# IGauge_V_2_2.net
KiCad netlist of a schematic drawn in EAGLE
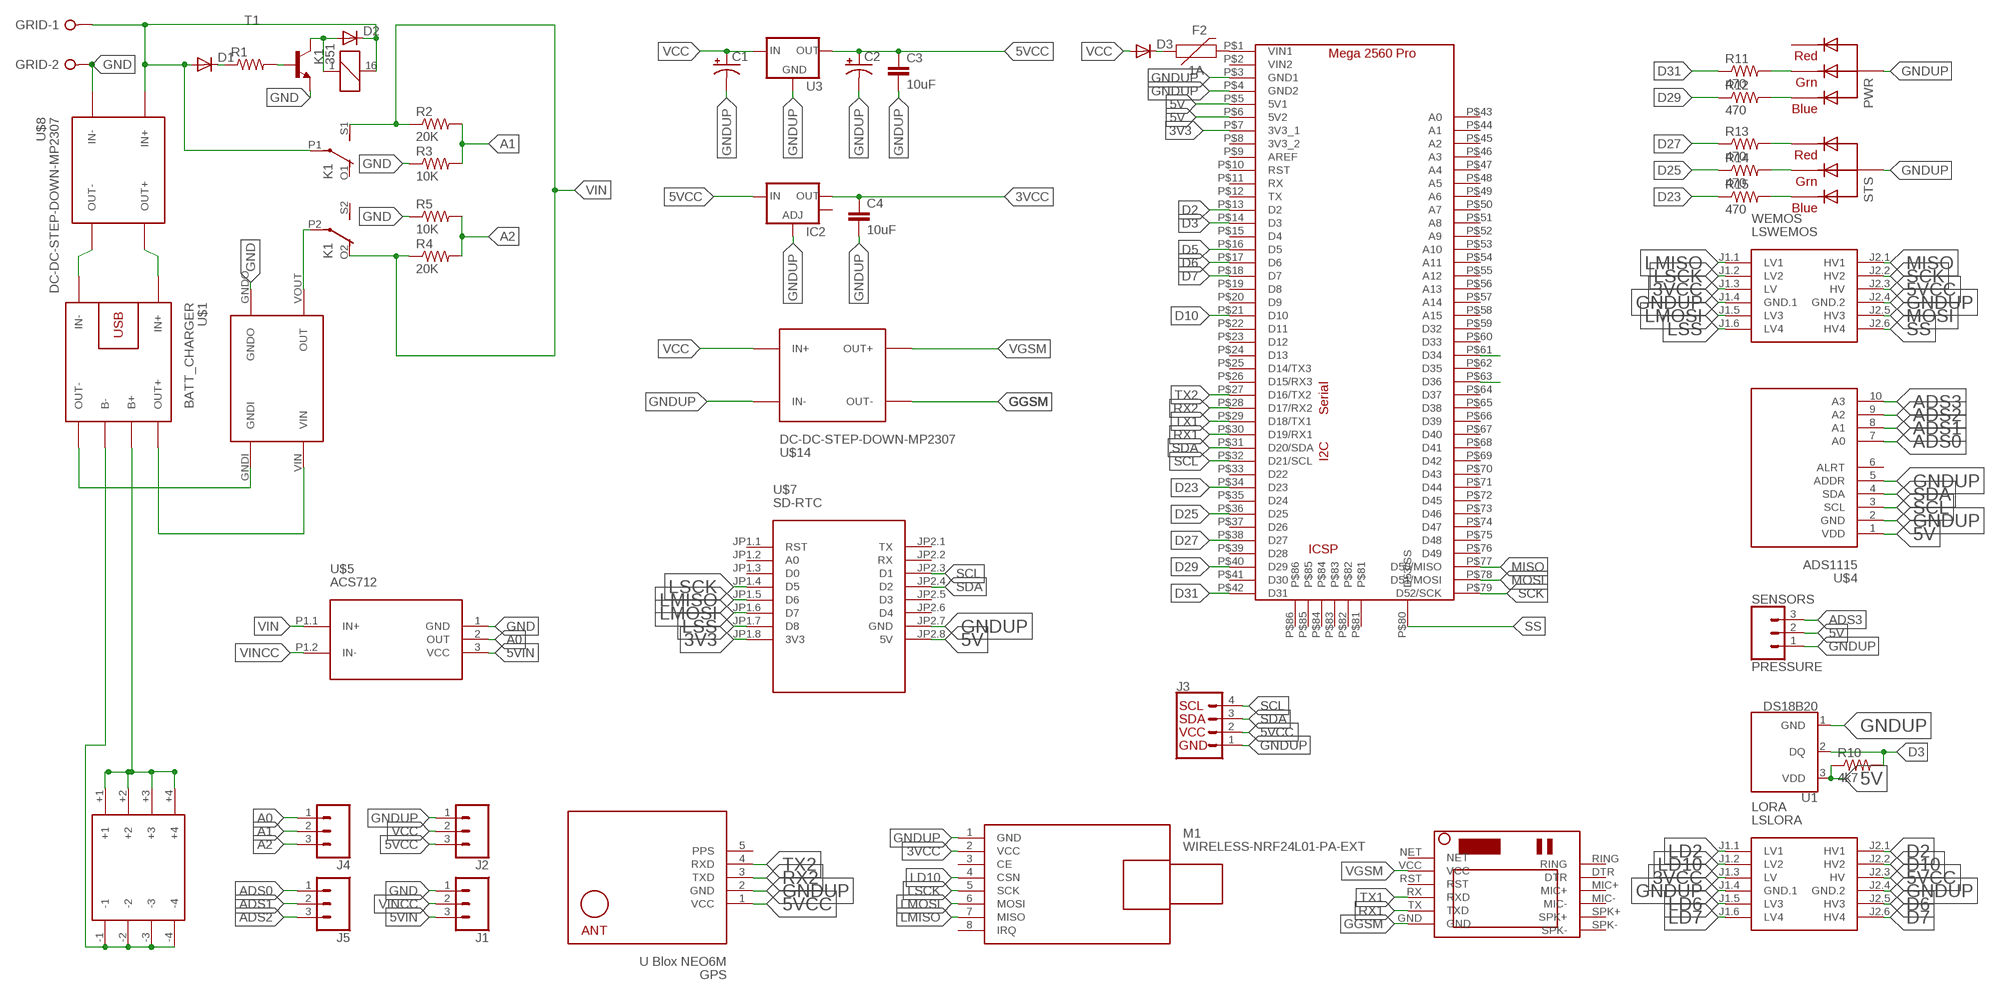
[diagram p0: schematic, sheet 1]

(export (version "E")
  (design (tool "Eeschema 10.0.6"))
  (components
    (comp (ref "C1")
      (value "CPOL-USD")
      (footprint "eagle-import:PANASONIC_D")
      (libsource (lib "eagle-import") (part "CPOL-USD"))
    )
    (comp (ref "C2")
      (value "CPOL-USD")
      (footprint "eagle-import:PANASONIC_D")
      (libsource (lib "eagle-import") (part "CPOL-USD"))
    )
    (comp (ref "C3")
      (value "10uF")
      (footprint "eagle-import:1206")
      (libsource (lib "eagle-import") (part "10UF-1206-6.3V-20%"))
    )
    (comp (ref "C4")
      (value "10uF")
      (footprint "eagle-import:1206")
      (libsource (lib "eagle-import") (part "10UF-1206-6.3V-20%"))
    )
    (comp (ref "D1")
      (value "DIODE-SOD106A-R")
      (footprint "eagle-import:SOD106A-R")
      (libsource (lib "eagle-import") (part "DIODE-SOD106A-R"))
    )
    (comp (ref "D2")
      (value "DIODE-SOD106A-R")
      (footprint "eagle-import:SOD106A-R")
      (libsource (lib "eagle-import") (part "DIODE-SOD106A-R"))
    )
    (comp (ref "D3")
      (value "DIODE-SOD106A-R")
      (footprint "eagle-import:SOD106A-R")
      (libsource (lib "eagle-import") (part "DIODE-SOD106A-R"))
    )
    (comp (ref "F2")
      (value "1A")
      (footprint "eagle-import:1206")
      (libsource (lib "eagle-import") (part "PPTC_HALF-AMP"))
    )
    (comp (ref "GPS")
      (value "U Blox NEO6M")
      (footprint "eagle-import:GPS-RECEIVER-NEO6M")
      (libsource (lib "eagle-import") (part "GPS-RECEIVER-NEO6M"))
    )
    (comp (ref "GRID")
      (value "W237-02P")
      (footprint "eagle-import:W237-132")
      (libsource (lib "eagle-import") (part "W237-02P"))
    )
    (comp (ref "IC2")
      (value "V_REG_LM1117SOT223")
      (footprint "eagle-import:SOT223")
      (libsource (lib "eagle-import") (part "V_REG_LM1117SOT223"))
    )
    (comp (ref "J1")
      (value "CONN_03")
      (footprint "eagle-import:1X03")
      (libsource (lib "eagle-import") (part "CONN_03"))
    )
    (comp (ref "J2")
      (value "CONN_03")
      (footprint "eagle-import:1X03")
      (libsource (lib "eagle-import") (part "CONN_03"))
    )
    (comp (ref "J3")
      (value "I2C_STANDARD")
      (footprint "eagle-import:1X04")
      (libsource (lib "eagle-import") (part "I2C_STANDARD"))
    )
    (comp (ref "J4")
      (value "CONN_03")
      (footprint "eagle-import:1X03")
      (libsource (lib "eagle-import") (part "CONN_03"))
    )
    (comp (ref "J5")
      (value "CONN_03")
      (footprint "eagle-import:1X03")
      (libsource (lib "eagle-import") (part "CONN_03"))
    )
    (comp (ref "K1")
      (value "351")
      (footprint "eagle-import:351")
      (libsource (lib "eagle-import") (part "351"))
    )
    (comp (ref "LORA")
      (value "LSLORA")
      (footprint "eagle-import:LEVEL-SHIFTER-4CH")
      (libsource (lib "eagle-import") (part "LEVEL-SHIFTER-4CH"))
    )
    (comp (ref "M1")
      (value "WIRELESS-NRF24L01-PA-EXT")
      (footprint "eagle-import:WIRELESS-NRF24L01-PA-EXT")
      (libsource (lib "eagle-import") (part "WIRELESS-NRF24L01-PA-EXT"))
    )
    (comp (ref "PWR")
      (value "RGBLED_CA-5MM")
      (footprint "eagle-import:LED5MMRGB")
      (libsource (lib "eagle-import") (part "RGBLED_CA-5MM"))
    )
    (comp (ref "R1")
      (value "R-US_R1206")
      (footprint "eagle-import:R1206")
      (libsource (lib "eagle-import") (part "resistor_R-US_R1206"))
    )
    (comp (ref "R2")
      (value "20K")
      (footprint "eagle-import:R1206")
      (libsource (lib "eagle-import") (part "resistor_R-US_R1206"))
    )
    (comp (ref "R3")
      (value "10K")
      (footprint "eagle-import:R1206")
      (libsource (lib "eagle-import") (part "resistor_R-US_R1206"))
    )
    (comp (ref "R4")
      (value "20K")
      (footprint "eagle-import:R1206")
      (libsource (lib "eagle-import") (part "resistor_R-US_R1206"))
    )
    (comp (ref "R5")
      (value "10K")
      (footprint "eagle-import:R1206")
      (libsource (lib "eagle-import") (part "resistor_R-US_R1206"))
    )
    (comp (ref "R10")
      (value "4k7")
      (footprint "eagle-import:M1406")
      (libsource (lib "eagle-import") (part "R-US_M1406"))
    )
    (comp (ref "R11")
      (value "470")
      (footprint "eagle-import:R1206")
      (libsource (lib "eagle-import") (part "resistor_R-US_R1206"))
    )
    (comp (ref "R12")
      (value "470")
      (footprint "eagle-import:R1206")
      (libsource (lib "eagle-import") (part "resistor_R-US_R1206"))
    )
    (comp (ref "R13")
      (value "470")
      (footprint "eagle-import:R1206")
      (libsource (lib "eagle-import") (part "resistor_R-US_R1206"))
    )
    (comp (ref "R14")
      (value "470")
      (footprint "eagle-import:R1206")
      (libsource (lib "eagle-import") (part "resistor_R-US_R1206"))
    )
    (comp (ref "R15")
      (value "470")
      (footprint "eagle-import:R1206")
      (libsource (lib "eagle-import") (part "resistor_R-US_R1206"))
    )
    (comp (ref "SENSORS")
      (value "PRESSURE")
      (footprint "eagle-import:MOLEX-1X3")
      (libsource (lib "eagle-import") (part "CONN_03POLAR"))
    )
    (comp (ref "STS")
      (value "RGBLED_CA-5MM")
      (footprint "eagle-import:LED5MMRGB")
      (libsource (lib "eagle-import") (part "RGBLED_CA-5MM"))
    )
    (comp (ref "T1")
      (value "-NPN-SOT23-EBC")
      (footprint "eagle-import:SOT23-EBC")
      (libsource (lib "eagle-import") (part "-NPN-SOT23-EBC"))
    )
    (comp (ref "U$1")
      (value "BATT_CHARGER")
      (footprint "eagle-import:BATTERY-CHARGER-LI-PROT")
      (libsource (lib "eagle-import") (part "BATTERY-CHARGER-LI-PROT"))
    )
    (comp (ref "U$2")
      (value "MT360_STEPUP")
      (footprint "eagle-import:MT360_STEPUP")
      (libsource (lib "eagle-import") (part "MT360_STEPUP"))
    )
    (comp (ref "U$3")
      (value "MEGAPROMINI")
      (footprint "eagle-import:MEGAPROMINI")
      (libsource (lib "eagle-import") (part "MEGAPROMINI"))
    )
    (comp (ref "U$4")
      (value "ADS1115")
      (footprint "eagle-import:ADC-4CH-ADS1115")
      (libsource (lib "eagle-import") (part "ADC-4CH-ADS1115"))
    )
    (comp (ref "U$5")
      (value "ACS712")
      (footprint "eagle-import:CURRENT-SENSOR-ACS712#IC")
      (libsource (lib "eagle-import") (part "CURRENT-SENSOR-ACS712#IC"))
    )
    (comp (ref "U$7")
      (value "SD-RTC")
      (footprint "eagle-import:WEMOS-D1-MINI-SHIELD")
      (libsource (lib "eagle-import") (part "WEMOS-D1-MINI-SHIELD"))
    )
    (comp (ref "U$8")
      (value "DC-DC-STEP-DOWN-MP2307")
      (footprint "eagle-import:DC-DC-STEP-DOWN-MP2307")
      (libsource (lib "eagle-import") (part "DC-DC-STEP-DOWN-MP2307"))
    )
    (comp (ref "U$9")
      (value "18650_4PCS_BATTERY_HOLDER")
      (footprint "eagle-import:18650_4PCS_BATTERY_HOLDER")
      (libsource (lib "eagle-import") (part "18650_4PCS_BATTERY_HOLDER"))
    )
    (comp (ref "U$10")
      (value "SIM800LMODULE")
      (footprint "eagle-import:SIM800LMODULE")
      (libsource (lib "eagle-import") (part "SIM800LMODULE"))
    )
    (comp (ref "U$14")
      (value "DC-DC-STEP-DOWN-MP2307")
      (footprint "eagle-import:DC-DC-STEP-DOWN-MP2307")
      (libsource (lib "eagle-import") (part "DC-DC-STEP-DOWN-MP2307"))
    )
    (comp (ref "U1")
      (value "DS18B20")
      (footprint "eagle-import:TO-92-AMMO")
      (libsource (lib "eagle-import") (part "DS18B20"))
    )
    (comp (ref "U3")
      (value "V_REG_78XX-TO-220")
      (footprint "eagle-import:TO-220-ALT")
      (libsource (lib "eagle-import") (part "V_REG_78XX-TO-220"))
    )
    (comp (ref "WEMOS")
      (value "LSWEMOS")
      (footprint "eagle-import:LEVEL-SHIFTER-4CH")
      (libsource (lib "eagle-import") (part "LEVEL-SHIFTER-4CH"))
    )
  )
  (nets
    (net (code "1") (name "/PPS") (class "Default")
      (node (ref "GPS") (pin "5") (pinfunction "PPS_5") (pintype "power_in"))
    )
    (net (code "2") (name "3V3") (class "Default")
      (node (ref "U$3") (pin "P$7") (pinfunction "3V3_1_P$7") (pintype "bidirectional"))
      (node (ref "U$7") (pin "JP1.8") (pinfunction "3V3_JP1.8") (pintype "power_in"))
    )
    (net (code "3") (name "3VCC") (class "Default")
      (node (ref "C4") (pin "1") (pinfunction "1_1") (pintype "passive"))
      (node (ref "IC2") (pin "2") (pinfunction "OUT_2") (pintype "output"))
      (node (ref "LORA") (pin "J1.3") (pinfunction "LV_J1.3") (pintype "power_in"))
      (node (ref "M1") (pin "2") (pinfunction "VCC_2") (pintype "power_in"))
      (node (ref "WEMOS") (pin "J1.3") (pinfunction "LV_J1.3") (pintype "power_in"))
    )
    (net (code "4") (name "5V") (class "Default")
      (node (ref "R10") (pin "1") (pinfunction "1_1") (pintype "passive"))
      (node (ref "SENSORS") (pin "2") (pinfunction "2_2") (pintype "passive"))
      (node (ref "U$3") (pin "P$5") (pinfunction "5V1_P$5") (pintype "bidirectional"))
      (node (ref "U$3") (pin "P$6") (pinfunction "5V2_P$6") (pintype "bidirectional"))
      (node (ref "U$4") (pin "1") (pinfunction "VDD_1") (pintype "power_in"))
      (node (ref "U$7") (pin "JP2.8") (pinfunction "5V_JP2.8") (pintype "power_in"))
      (node (ref "U1") (pin "3") (pinfunction "VDD_3") (pintype "power_in"))
    )
    (net (code "5") (name "5VCC") (class "Default")
      (node (ref "C2") (pin "+") (pinfunction "+_+") (pintype "passive"))
      (node (ref "C3") (pin "1") (pinfunction "1_1") (pintype "passive"))
      (node (ref "GPS") (pin "1") (pinfunction "VCC_1") (pintype "bidirectional"))
      (node (ref "IC2") (pin "3") (pinfunction "IN_3") (pintype "input"))
      (node (ref "J2") (pin "3") (pinfunction "3_3") (pintype "passive"))
      (node (ref "J3") (pin "2") (pinfunction "2_2") (pintype "power_in"))
      (node (ref "LORA") (pin "J2.3") (pinfunction "HV_J2.3") (pintype "power_in"))
      (node (ref "U3") (pin "OUT") (pinfunction "OUT_OUT") (pintype "passive"))
      (node (ref "WEMOS") (pin "J2.3") (pinfunction "HV_J2.3") (pintype "power_in"))
    )
    (net (code "6") (name "5VIN") (class "Default")
      (node (ref "J1") (pin "3") (pinfunction "3_3") (pintype "passive"))
      (node (ref "U$5") (pin "3") (pinfunction "VCC_3") (pintype "power_in"))
    )
    (net (code "7") (name "A0") (class "Default")
      (node (ref "J4") (pin "1") (pinfunction "1_1") (pintype "passive"))
      (node (ref "U$5") (pin "2") (pinfunction "OUT_2") (pintype "output"))
    )
    (net (code "8") (name "A1") (class "Default")
      (node (ref "J4") (pin "2") (pinfunction "2_2") (pintype "passive"))
      (node (ref "R2") (pin "2") (pinfunction "2_2") (pintype "passive"))
      (node (ref "R3") (pin "2") (pinfunction "2_2") (pintype "passive"))
    )
    (net (code "9") (name "A2") (class "Default")
      (node (ref "J4") (pin "3") (pinfunction "3_3") (pintype "passive"))
      (node (ref "R4") (pin "2") (pinfunction "2_2") (pintype "passive"))
      (node (ref "R5") (pin "2") (pinfunction "2_2") (pintype "passive"))
    )
    (net (code "10") (name "ADS0") (class "Default")
      (node (ref "J5") (pin "1") (pinfunction "1_1") (pintype "passive"))
      (node (ref "U$4") (pin "7") (pinfunction "A0_7") (pintype "input"))
    )
    (net (code "11") (name "ADS1") (class "Default")
      (node (ref "J5") (pin "2") (pinfunction "2_2") (pintype "passive"))
      (node (ref "U$4") (pin "8") (pinfunction "A1_8") (pintype "input"))
    )
    (net (code "12") (name "ADS2") (class "Default")
      (node (ref "J5") (pin "3") (pinfunction "3_3") (pintype "passive"))
      (node (ref "U$4") (pin "9") (pinfunction "A2_9") (pintype "input"))
    )
    (net (code "13") (name "ADS3") (class "Default")
      (node (ref "SENSORS") (pin "3") (pinfunction "3_3") (pintype "passive"))
      (node (ref "U$4") (pin "10") (pinfunction "A3_10") (pintype "input"))
    )
    (net (code "14") (name "D2") (class "Default")
      (node (ref "LORA") (pin "J2.1") (pinfunction "HV1_J2.1") (pintype "bidirectional"))
      (node (ref "U$3") (pin "P$13") (pinfunction "D2_P$13") (pintype "bidirectional"))
    )
    (net (code "15") (name "D3") (class "Default")
      (node (ref "R10") (pin "2") (pinfunction "2_2") (pintype "passive"))
      (node (ref "U$3") (pin "P$14") (pinfunction "D3_P$14") (pintype "bidirectional"))
      (node (ref "U1") (pin "2") (pinfunction "DQ_2") (pintype "bidirectional"))
    )
    (net (code "16") (name "D5") (class "Default")
      (node (ref "U$3") (pin "P$16") (pinfunction "D5_P$16") (pintype "bidirectional"))
    )
    (net (code "17") (name "D6") (class "Default")
      (node (ref "LORA") (pin "J2.5") (pinfunction "HV3_J2.5") (pintype "bidirectional"))
      (node (ref "U$3") (pin "P$17") (pinfunction "D6_P$17") (pintype "bidirectional"))
    )
    (net (code "18") (name "D7") (class "Default")
      (node (ref "LORA") (pin "J2.6") (pinfunction "HV4_J2.6") (pintype "bidirectional"))
      (node (ref "U$3") (pin "P$18") (pinfunction "D7_P$18") (pintype "bidirectional"))
    )
    (net (code "19") (name "D10") (class "Default")
      (node (ref "LORA") (pin "J2.2") (pinfunction "HV2_J2.2") (pintype "bidirectional"))
      (node (ref "U$3") (pin "P$21") (pinfunction "D10_P$21") (pintype "bidirectional"))
    )
    (net (code "20") (name "D23") (class "Default")
      (node (ref "R15") (pin "1") (pinfunction "1_1") (pintype "passive"))
      (node (ref "U$3") (pin "P$34") (pinfunction "D23_P$34") (pintype "bidirectional"))
    )
    (net (code "21") (name "D25") (class "Default")
      (node (ref "R14") (pin "1") (pinfunction "1_1") (pintype "passive"))
      (node (ref "U$3") (pin "P$36") (pinfunction "D25_P$36") (pintype "bidirectional"))
    )
    (net (code "22") (name "D27") (class "Default")
      (node (ref "R13") (pin "1") (pinfunction "1_1") (pintype "passive"))
      (node (ref "U$3") (pin "P$38") (pinfunction "D27_P$38") (pintype "bidirectional"))
    )
    (net (code "23") (name "D29") (class "Default")
      (node (ref "R12") (pin "1") (pinfunction "1_1") (pintype "passive"))
      (node (ref "U$3") (pin "P$40") (pinfunction "D29_P$40") (pintype "bidirectional"))
    )
    (net (code "24") (name "D31") (class "Default")
      (node (ref "R11") (pin "1") (pinfunction "1_1") (pintype "passive"))
      (node (ref "U$3") (pin "P$42") (pinfunction "D31_P$42") (pintype "bidirectional"))
    )
    (net (code "25") (name "GGSM") (class "Default")
      (node (ref "U$10") (pin "GND") (pinfunction "GND_GND") (pintype "bidirectional"))
      (node (ref "U$14") (pin "OUT-") (pinfunction "OUT-_OUT-") (pintype "bidirectional"))
    )
    (net (code "26") (name "GND") (class "Default")
      (node (ref "D1") (pin "A") (pinfunction "A_A") (pintype "passive"))
      (node (ref "D2") (pin "C") (pinfunction "C_C") (pintype "passive"))
      (node (ref "GRID") (pin "1") (pinfunction "KL_1") (pintype "passive"))
      (node (ref "GRID") (pin "2") (pinfunction "KL_2") (pintype "passive"))
      (node (ref "J1") (pin "1") (pinfunction "1_1") (pintype "passive"))
      (node (ref "K1") (pin "16") (pinfunction "2_16") (pintype "passive"))
      (node (ref "K1") (pin "P1") (pinfunction "P_P1") (pintype "passive"))
      (node (ref "R3") (pin "1") (pinfunction "1_1") (pintype "passive"))
      (node (ref "R5") (pin "1") (pinfunction "1_1") (pintype "passive"))
      (node (ref "T1") (pin "E") (pinfunction "E_E") (pintype "passive"))
      (node (ref "U$2") (pin "GNDO") (pinfunction "GNDO_GNDO") (pintype "bidirectional"))
      (node (ref "U$5") (pin "1") (pinfunction "GND_1") (pintype "power_in"))
      (node (ref "U$8") (pin "IN+") (pinfunction "IN+_IN+") (pintype "bidirectional"))
      (node (ref "U$8") (pin "IN-") (pinfunction "IN-_IN-") (pintype "bidirectional"))
    )
    (net (code "27") (name "GNDUP") (class "Default")
      (node (ref "C1") (pin "-") (pinfunction "-_-") (pintype "passive"))
      (node (ref "C2") (pin "-") (pinfunction "-_-") (pintype "passive"))
      (node (ref "C3") (pin "2") (pinfunction "2_2") (pintype "passive"))
      (node (ref "C4") (pin "2") (pinfunction "2_2") (pintype "passive"))
      (node (ref "GPS") (pin "2") (pinfunction "GND_2") (pintype "bidirectional"))
      (node (ref "IC2") (pin "1") (pinfunction "ADJ_1") (pintype "input"))
      (node (ref "J2") (pin "1") (pinfunction "1_1") (pintype "passive"))
      (node (ref "J3") (pin "1") (pinfunction "1_1") (pintype "power_in"))
      (node (ref "LORA") (pin "J1.4") (pinfunction "GND.1_J1.4") (pintype "power_in"))
      (node (ref "LORA") (pin "J2.4") (pinfunction "GND.2_J2.4") (pintype "power_in"))
      (node (ref "M1") (pin "1") (pinfunction "GND_1") (pintype "power_in"))
      (node (ref "PWR") (pin "2") (pinfunction "VCC_2") (pintype "bidirectional"))
      (node (ref "SENSORS") (pin "1") (pinfunction "1_1") (pintype "passive"))
      (node (ref "STS") (pin "2") (pinfunction "VCC_2") (pintype "bidirectional"))
      (node (ref "U$1") (pin "IN-") (pinfunction "IN-_IN-") (pintype "bidirectional"))
      (node (ref "U$14") (pin "IN-") (pinfunction "IN-_IN-") (pintype "bidirectional"))
      (node (ref "U$3") (pin "P$3") (pinfunction "GND1_P$3") (pintype "bidirectional"))
      (node (ref "U$3") (pin "P$4") (pinfunction "GND2_P$4") (pintype "bidirectional"))
      (node (ref "U$4") (pin "2") (pinfunction "GND_2") (pintype "power_in"))
      (node (ref "U$4") (pin "5") (pinfunction "ADDR_5") (pintype "bidirectional"))
      (node (ref "U$7") (pin "JP2.7") (pinfunction "GND_JP2.7") (pintype "power_in"))
      (node (ref "U$8") (pin "OUT-") (pinfunction "OUT-_OUT-") (pintype "bidirectional"))
      (node (ref "U1") (pin "1") (pinfunction "GND_1") (pintype "power_in"))
      (node (ref "U3") (pin "GND") (pinfunction "GND_GND") (pintype "input"))
      (node (ref "WEMOS") (pin "J1.4") (pinfunction "GND.1_J1.4") (pintype "power_in"))
      (node (ref "WEMOS") (pin "J2.4") (pinfunction "GND.2_J2.4") (pintype "power_in"))
    )
    (net (code "28") (name "LD2") (class "Default")
      (node (ref "LORA") (pin "J1.1") (pinfunction "LV1_J1.1") (pintype "bidirectional"))
    )
    (net (code "29") (name "LD6") (class "Default")
      (node (ref "LORA") (pin "J1.5") (pinfunction "LV3_J1.5") (pintype "bidirectional"))
    )
    (net (code "30") (name "LD7") (class "Default")
      (node (ref "LORA") (pin "J1.6") (pinfunction "LV4_J1.6") (pintype "bidirectional"))
    )
    (net (code "31") (name "LD10") (class "Default")
      (node (ref "LORA") (pin "J1.2") (pinfunction "LV2_J1.2") (pintype "bidirectional"))
      (node (ref "M1") (pin "4") (pinfunction "CSN_4") (pintype "bidirectional"))
    )
    (net (code "32") (name "LMISO") (class "Default")
      (node (ref "M1") (pin "7") (pinfunction "MISO_7") (pintype "bidirectional"))
      (node (ref "U$7") (pin "JP1.5") (pinfunction "D6_JP1.5") (pintype "bidirectional"))
      (node (ref "WEMOS") (pin "J1.1") (pinfunction "LV1_J1.1") (pintype "bidirectional"))
    )
    (net (code "33") (name "LMOSI") (class "Default")
      (node (ref "M1") (pin "6") (pinfunction "MOSI_6") (pintype "bidirectional"))
      (node (ref "U$7") (pin "JP1.6") (pinfunction "D7_JP1.6") (pintype "bidirectional"))
      (node (ref "WEMOS") (pin "J1.5") (pinfunction "LV3_J1.5") (pintype "bidirectional"))
    )
    (net (code "34") (name "LSCK") (class "Default")
      (node (ref "M1") (pin "5") (pinfunction "SCK_5") (pintype "bidirectional"))
      (node (ref "U$7") (pin "JP1.4") (pinfunction "D5_JP1.4") (pintype "bidirectional"))
      (node (ref "WEMOS") (pin "J1.2") (pinfunction "LV2_J1.2") (pintype "bidirectional"))
    )
    (net (code "35") (name "LSS") (class "Default")
      (node (ref "U$7") (pin "JP1.7") (pinfunction "D8_JP1.7") (pintype "bidirectional"))
      (node (ref "WEMOS") (pin "J1.6") (pinfunction "LV4_J1.6") (pintype "bidirectional"))
    )
    (net (code "36") (name "MISO") (class "Default")
      (node (ref "U$3") (pin "P$77") (pinfunction "D50/MISO_P$77") (pintype "bidirectional"))
      (node (ref "WEMOS") (pin "J2.1") (pinfunction "HV1_J2.1") (pintype "bidirectional"))
    )
    (net (code "37") (name "MOSI") (class "Default")
      (node (ref "U$3") (pin "P$78") (pinfunction "D51/MOSI_P$78") (pintype "bidirectional"))
      (node (ref "WEMOS") (pin "J2.5") (pinfunction "HV3_J2.5") (pintype "bidirectional"))
    )
    (net (code "38") (name "Net-(D1-PadC)") (class "Default")
      (node (ref "D1") (pin "C") (pinfunction "C_C") (pintype "passive"))
      (node (ref "R1") (pin "1") (pinfunction "1_1") (pintype "passive"))
    )
    (net (code "39") (name "Net-(D2-PadA)") (class "Default")
      (node (ref "D2") (pin "A") (pinfunction "A_A") (pintype "passive"))
      (node (ref "K1") (pin "1") (pinfunction "1_1") (pintype "passive"))
      (node (ref "T1") (pin "C") (pinfunction "C_C") (pintype "passive"))
    )
    (net (code "40") (name "Net-(D3-PadC)") (class "Default")
      (node (ref "D3") (pin "C") (pinfunction "C_C") (pintype "passive"))
      (node (ref "F2") (pin "1") (pinfunction "1_1") (pintype "bidirectional"))
    )
    (net (code "41") (name "Net-(K1C-P)") (class "Default")
      (node (ref "K1") (pin "P2") (pinfunction "P_P2") (pintype "passive"))
      (node (ref "U$2") (pin "VOUT") (pinfunction "OUT_VOUT") (pintype "bidirectional"))
    )
    (net (code "42") (name "Net-(PWR-BLUE)") (class "Default")
      (node (ref "PWR") (pin "4") (pinfunction "BLUE_4") (pintype "bidirectional"))
      (node (ref "R12") (pin "2") (pinfunction "2_2") (pintype "passive"))
    )
    (net (code "43") (name "Net-(PWR-GREEN)") (class "Default")
      (node (ref "PWR") (pin "3") (pinfunction "GREEN_3") (pintype "bidirectional"))
      (node (ref "R11") (pin "2") (pinfunction "2_2") (pintype "passive"))
    )
    (net (code "44") (name "Net-(R1-Pad2)") (class "Default")
      (node (ref "R1") (pin "2") (pinfunction "2_2") (pintype "passive"))
      (node (ref "T1") (pin "B") (pinfunction "B_B") (pintype "passive"))
    )
    (net (code "45") (name "Net-(STS-BLUE)") (class "Default")
      (node (ref "R15") (pin "2") (pinfunction "2_2") (pintype "passive"))
      (node (ref "STS") (pin "4") (pinfunction "BLUE_4") (pintype "bidirectional"))
    )
    (net (code "46") (name "Net-(STS-GREEN)") (class "Default")
      (node (ref "R14") (pin "2") (pinfunction "2_2") (pintype "passive"))
      (node (ref "STS") (pin "3") (pinfunction "GREEN_3") (pintype "bidirectional"))
    )
    (net (code "47") (name "Net-(STS-RED)") (class "Default")
      (node (ref "R13") (pin "2") (pinfunction "2_2") (pintype "passive"))
      (node (ref "STS") (pin "1") (pinfunction "RED_1") (pintype "bidirectional"))
    )
    (net (code "48") (name "Net-(U$1-PadB+)") (class "Default")
      (node (ref "U$1") (pin "B+") (pinfunction "B+_B+") (pintype "bidirectional"))
      (node (ref "U$9") (pin "+1") (pinfunction "+1_+1") (pintype "bidirectional"))
      (node (ref "U$9") (pin "+2") (pinfunction "+2_+2") (pintype "bidirectional"))
      (node (ref "U$9") (pin "+3") (pinfunction "+3_+3") (pintype "bidirectional"))
      (node (ref "U$9") (pin "+4") (pinfunction "+4_+4") (pintype "bidirectional"))
    )
    (net (code "49") (name "Net-(U$1-PadB-)") (class "Default")
      (node (ref "U$1") (pin "B-") (pinfunction "B-_B-") (pintype "bidirectional"))
      (node (ref "U$9") (pin "-1") (pinfunction "-1_-1") (pintype "bidirectional"))
      (node (ref "U$9") (pin "-2") (pinfunction "-2_-2") (pintype "bidirectional"))
      (node (ref "U$9") (pin "-3") (pinfunction "-3_-3") (pintype "bidirectional"))
      (node (ref "U$9") (pin "-4") (pinfunction "-4_-4") (pintype "bidirectional"))
    )
    (net (code "50") (name "Net-(U$1-PadIN+)") (class "Default")
      (node (ref "U$1") (pin "IN+") (pinfunction "IN+_IN+") (pintype "bidirectional"))
      (node (ref "U$8") (pin "OUT+") (pinfunction "OUT+_OUT+") (pintype "bidirectional"))
    )
    (net (code "51") (name "Net-(U$1-PadOUT+)") (class "Default")
      (node (ref "U$1") (pin "OUT+") (pinfunction "OUT+_OUT+") (pintype "bidirectional"))
      (node (ref "U$2") (pin "VIN") (pinfunction "VIN_VIN") (pintype "bidirectional"))
    )
    (net (code "52") (name "Net-(U$1-PadOUT-)") (class "Default")
      (node (ref "U$1") (pin "OUT-") (pinfunction "OUT-_OUT-") (pintype "bidirectional"))
      (node (ref "U$2") (pin "GNDI") (pinfunction "GNDI_GNDI") (pintype "bidirectional"))
    )
    (net (code "53") (name "Net-(U$3-VIN1)") (class "Default")
      (node (ref "F2") (pin "2") (pinfunction "2_2") (pintype "bidirectional"))
      (node (ref "U$3") (pin "P$1") (pinfunction "VIN1_P$1") (pintype "bidirectional"))
    )
    (net (code "54") (name "RX1") (class "Default")
      (node (ref "U$10") (pin "TX") (pinfunction "TXD_TX") (pintype "bidirectional"))
      (node (ref "U$3") (pin "P$30") (pinfunction "D19/RX1_P$30") (pintype "bidirectional"))
    )
    (net (code "55") (name "RX2") (class "Default")
      (node (ref "GPS") (pin "3") (pinfunction "TXD_3") (pintype "bidirectional"))
      (node (ref "U$3") (pin "P$28") (pinfunction "D17/RX2_P$28") (pintype "bidirectional"))
    )
    (net (code "56") (name "SCK") (class "Default")
      (node (ref "U$3") (pin "P$79") (pinfunction "D52/SCK_P$79") (pintype "bidirectional"))
      (node (ref "WEMOS") (pin "J2.2") (pinfunction "HV2_J2.2") (pintype "bidirectional"))
    )
    (net (code "57") (name "SCL") (class "Default")
      (node (ref "J3") (pin "4") (pinfunction "4_4") (pintype "passive"))
      (node (ref "U$3") (pin "P$32") (pinfunction "D21/SCL_P$32") (pintype "bidirectional"))
      (node (ref "U$4") (pin "3") (pinfunction "SCL_3") (pintype "bidirectional"))
      (node (ref "U$7") (pin "JP2.3") (pinfunction "D1_JP2.3") (pintype "bidirectional"))
    )
    (net (code "58") (name "SDA") (class "Default")
      (node (ref "J3") (pin "3") (pinfunction "3_3") (pintype "passive"))
      (node (ref "U$3") (pin "P$31") (pinfunction "D20/SDA_P$31") (pintype "bidirectional"))
      (node (ref "U$4") (pin "4") (pinfunction "SDA_4") (pintype "bidirectional"))
      (node (ref "U$7") (pin "JP2.4") (pinfunction "D2_JP2.4") (pintype "bidirectional"))
    )
    (net (code "59") (name "SS") (class "Default")
      (node (ref "U$3") (pin "P$80") (pinfunction "D53/SS_P$80") (pintype "bidirectional"))
      (node (ref "WEMOS") (pin "J2.6") (pinfunction "HV4_J2.6") (pintype "bidirectional"))
    )
    (net (code "60") (name "TX1") (class "Default")
      (node (ref "U$10") (pin "RX") (pinfunction "RXD_RX") (pintype "bidirectional"))
      (node (ref "U$3") (pin "P$29") (pinfunction "D18/TX1_P$29") (pintype "bidirectional"))
    )
    (net (code "61") (name "TX2") (class "Default")
      (node (ref "GPS") (pin "4") (pinfunction "RXD_4") (pintype "power_in"))
      (node (ref "U$3") (pin "P$27") (pinfunction "D16/TX2_P$27") (pintype "bidirectional"))
    )
    (net (code "62") (name "VCC") (class "Default")
      (node (ref "C1") (pin "+") (pinfunction "+_+") (pintype "passive"))
      (node (ref "D3") (pin "A") (pinfunction "A_A") (pintype "passive"))
      (node (ref "J2") (pin "2") (pinfunction "2_2") (pintype "passive"))
      (node (ref "U$14") (pin "IN+") (pinfunction "IN+_IN+") (pintype "bidirectional"))
      (node (ref "U3") (pin "IN") (pinfunction "IN_IN") (pintype "input"))
    )
    (net (code "63") (name "VGSM") (class "Default")
      (node (ref "U$10") (pin "VCC") (pinfunction "VCC_VCC") (pintype "bidirectional"))
      (node (ref "U$14") (pin "OUT+") (pinfunction "OUT+_OUT+") (pintype "bidirectional"))
    )
    (net (code "64") (name "VIN") (class "Default")
      (node (ref "K1") (pin "O2") (pinfunction "O_O2") (pintype "passive"))
      (node (ref "K1") (pin "S1") (pinfunction "S_S1") (pintype "passive"))
      (node (ref "R2") (pin "1") (pinfunction "1_1") (pintype "passive"))
      (node (ref "R4") (pin "1") (pinfunction "1_1") (pintype "passive"))
      (node (ref "U$5") (pin "P1.1") (pinfunction "IN+_P1.1") (pintype "bidirectional"))
    )
    (net (code "65") (name "VINCC") (class "Default")
      (node (ref "J1") (pin "2") (pinfunction "2_2") (pintype "passive"))
      (node (ref "U$5") (pin "P1.2") (pinfunction "IN-_P1.2") (pintype "bidirectional"))
    )
    (net (code "66") (name "unconnected-(IC2-OUT-Pad4)") (class "Default")
      (node (ref "IC2") (pin "4") (pinfunction "OUT_4") (pintype "output"))
    )
    (net (code "67") (name "unconnected-(K1B-O-PadO1)") (class "Default")
      (node (ref "K1") (pin "O1") (pinfunction "O_O1") (pintype "passive"))
    )
    (net (code "68") (name "unconnected-(K1C-S-PadS2)") (class "Default")
      (node (ref "K1") (pin "S2") (pinfunction "S_S2") (pintype "passive"))
    )
    (net (code "69") (name "unconnected-(M1-CE-Pad3)") (class "Default")
      (node (ref "M1") (pin "3") (pinfunction "CE_3") (pintype "bidirectional"))
    )
    (net (code "70") (name "unconnected-(M1-IRQ-Pad8)") (class "Default")
      (node (ref "M1") (pin "8") (pinfunction "IRQ_8") (pintype "bidirectional"))
    )
    (net (code "71") (name "unconnected-(PWR-RED-Pad1)") (class "Default")
      (node (ref "PWR") (pin "1") (pinfunction "RED_1") (pintype "bidirectional"))
    )
    (net (code "72") (name "unconnected-(U$3-3V3_2-PadP$8)") (class "Default")
      (node (ref "U$3") (pin "P$8") (pinfunction "3V3_2_P$8") (pintype "bidirectional"))
    )
    (net (code "73") (name "unconnected-(U$3-A0-PadP$43)") (class "Default")
      (node (ref "U$3") (pin "P$43") (pinfunction "A0_P$43") (pintype "bidirectional"))
    )
    (net (code "74") (name "unconnected-(U$3-A1-PadP$44)") (class "Default")
      (node (ref "U$3") (pin "P$44") (pinfunction "A1_P$44") (pintype "bidirectional"))
    )
    (net (code "75") (name "unconnected-(U$3-A2-PadP$45)") (class "Default")
      (node (ref "U$3") (pin "P$45") (pinfunction "A2_P$45") (pintype "bidirectional"))
    )
    (net (code "76") (name "unconnected-(U$3-A3-PadP$46)") (class "Default")
      (node (ref "U$3") (pin "P$46") (pinfunction "A3_P$46") (pintype "bidirectional"))
    )
    (net (code "77") (name "unconnected-(U$3-A4-PadP$47)") (class "Default")
      (node (ref "U$3") (pin "P$47") (pinfunction "A4_P$47") (pintype "bidirectional"))
    )
    (net (code "78") (name "unconnected-(U$3-A5-PadP$48)") (class "Default")
      (node (ref "U$3") (pin "P$48") (pinfunction "A5_P$48") (pintype "bidirectional"))
    )
    (net (code "79") (name "unconnected-(U$3-A6-PadP$49)") (class "Default")
      (node (ref "U$3") (pin "P$49") (pinfunction "A6_P$49") (pintype "bidirectional"))
    )
    (net (code "80") (name "unconnected-(U$3-A7-PadP$50)") (class "Default")
      (node (ref "U$3") (pin "P$50") (pinfunction "A7_P$50") (pintype "bidirectional"))
    )
    (net (code "81") (name "unconnected-(U$3-A8-PadP$51)") (class "Default")
      (node (ref "U$3") (pin "P$51") (pinfunction "A8_P$51") (pintype "bidirectional"))
    )
    (net (code "82") (name "unconnected-(U$3-A9-PadP$52)") (class "Default")
      (node (ref "U$3") (pin "P$52") (pinfunction "A9_P$52") (pintype "bidirectional"))
    )
    (net (code "83") (name "unconnected-(U$3-A10-PadP$53)") (class "Default")
      (node (ref "U$3") (pin "P$53") (pinfunction "A10_P$53") (pintype "bidirectional"))
    )
    (net (code "84") (name "unconnected-(U$3-A11-PadP$54)") (class "Default")
      (node (ref "U$3") (pin "P$54") (pinfunction "A11_P$54") (pintype "bidirectional"))
    )
    (net (code "85") (name "unconnected-(U$3-A12-PadP$55)") (class "Default")
      (node (ref "U$3") (pin "P$55") (pinfunction "A12_P$55") (pintype "bidirectional"))
    )
    (net (code "86") (name "unconnected-(U$3-A13-PadP$56)") (class "Default")
      (node (ref "U$3") (pin "P$56") (pinfunction "A13_P$56") (pintype "bidirectional"))
    )
    (net (code "87") (name "unconnected-(U$3-A14-PadP$57)") (class "Default")
      (node (ref "U$3") (pin "P$57") (pinfunction "A14_P$57") (pintype "bidirectional"))
    )
    (net (code "88") (name "unconnected-(U$3-A15-PadP$58)") (class "Default")
      (node (ref "U$3") (pin "P$58") (pinfunction "A15_P$58") (pintype "bidirectional"))
    )
    (net (code "89") (name "unconnected-(U$3-AREF-PadP$9)") (class "Default")
      (node (ref "U$3") (pin "P$9") (pinfunction "AREF_P$9") (pintype "bidirectional"))
    )
    (net (code "90") (name "unconnected-(U$3-D4-PadP$15)") (class "Default")
      (node (ref "U$3") (pin "P$15") (pinfunction "D4_P$15") (pintype "bidirectional"))
    )
    (net (code "91") (name "unconnected-(U$3-D8-PadP$19)") (class "Default")
      (node (ref "U$3") (pin "P$19") (pinfunction "D8_P$19") (pintype "bidirectional"))
    )
    (net (code "92") (name "unconnected-(U$3-D9-PadP$20)") (class "Default")
      (node (ref "U$3") (pin "P$20") (pinfunction "D9_P$20") (pintype "bidirectional"))
    )
    (net (code "93") (name "unconnected-(U$3-D11-PadP$22)") (class "Default")
      (node (ref "U$3") (pin "P$22") (pinfunction "D11_P$22") (pintype "bidirectional"))
    )
    (net (code "94") (name "unconnected-(U$3-D12-PadP$23)") (class "Default")
      (node (ref "U$3") (pin "P$23") (pinfunction "D12_P$23") (pintype "bidirectional"))
    )
    (net (code "95") (name "unconnected-(U$3-D13-PadP$24)") (class "Default")
      (node (ref "U$3") (pin "P$24") (pinfunction "D13_P$24") (pintype "bidirectional"))
    )
    (net (code "96") (name "unconnected-(U$3-D14{slash}TX3-PadP$25)") (class "Default")
      (node (ref "U$3") (pin "P$25") (pinfunction "D14/TX3_P$25") (pintype "bidirectional"))
    )
    (net (code "97") (name "unconnected-(U$3-D15{slash}RX3-PadP$26)") (class "Default")
      (node (ref "U$3") (pin "P$26") (pinfunction "D15/RX3_P$26") (pintype "bidirectional"))
    )
    (net (code "98") (name "unconnected-(U$3-D22-PadP$33)") (class "Default")
      (node (ref "U$3") (pin "P$33") (pinfunction "D22_P$33") (pintype "bidirectional"))
    )
    (net (code "99") (name "unconnected-(U$3-D24-PadP$35)") (class "Default")
      (node (ref "U$3") (pin "P$35") (pinfunction "D24_P$35") (pintype "bidirectional"))
    )
    (net (code "100") (name "unconnected-(U$3-D26-PadP$37)") (class "Default")
      (node (ref "U$3") (pin "P$37") (pinfunction "D26_P$37") (pintype "bidirectional"))
    )
    (net (code "101") (name "unconnected-(U$3-D28-PadP$39)") (class "Default")
      (node (ref "U$3") (pin "P$39") (pinfunction "D28_P$39") (pintype "bidirectional"))
    )
    (net (code "102") (name "unconnected-(U$3-D30-PadP$41)") (class "Default")
      (node (ref "U$3") (pin "P$41") (pinfunction "D30_P$41") (pintype "bidirectional"))
    )
    (net (code "103") (name "unconnected-(U$3-D32-PadP$59)") (class "Default")
      (node (ref "U$3") (pin "P$59") (pinfunction "D32_P$59") (pintype "bidirectional"))
    )
    (net (code "104") (name "unconnected-(U$3-D33-PadP$60)") (class "Default")
      (node (ref "U$3") (pin "P$60") (pinfunction "D33_P$60") (pintype "bidirectional"))
    )
    (net (code "105") (name "unconnected-(U$3-D34-PadP$61)") (class "Default")
      (node (ref "U$3") (pin "P$61") (pinfunction "D34_P$61") (pintype "bidirectional"))
    )
    (net (code "106") (name "unconnected-(U$3-D35-PadP$62)") (class "Default")
      (node (ref "U$3") (pin "P$62") (pinfunction "D35_P$62") (pintype "bidirectional"))
    )
    (net (code "107") (name "unconnected-(U$3-D36-PadP$63)") (class "Default")
      (node (ref "U$3") (pin "P$63") (pinfunction "D36_P$63") (pintype "bidirectional"))
    )
    (net (code "108") (name "unconnected-(U$3-D37-PadP$64)") (class "Default")
      (node (ref "U$3") (pin "P$64") (pinfunction "D37_P$64") (pintype "bidirectional"))
    )
    (net (code "109") (name "unconnected-(U$3-D38-PadP$65)") (class "Default")
      (node (ref "U$3") (pin "P$65") (pinfunction "D38_P$65") (pintype "bidirectional"))
    )
    (net (code "110") (name "unconnected-(U$3-D39-PadP$66)") (class "Default")
      (node (ref "U$3") (pin "P$66") (pinfunction "D39_P$66") (pintype "bidirectional"))
    )
    (net (code "111") (name "unconnected-(U$3-D40-PadP$67)") (class "Default")
      (node (ref "U$3") (pin "P$67") (pinfunction "D40_P$67") (pintype "bidirectional"))
    )
    (net (code "112") (name "unconnected-(U$3-D41-PadP$68)") (class "Default")
      (node (ref "U$3") (pin "P$68") (pinfunction "D41_P$68") (pintype "bidirectional"))
    )
    (net (code "113") (name "unconnected-(U$3-D42-PadP$69)") (class "Default")
      (node (ref "U$3") (pin "P$69") (pinfunction "D42_P$69") (pintype "bidirectional"))
    )
    (net (code "114") (name "unconnected-(U$3-D43-PadP$70)") (class "Default")
      (node (ref "U$3") (pin "P$70") (pinfunction "D43_P$70") (pintype "bidirectional"))
    )
    (net (code "115") (name "unconnected-(U$3-D44-PadP$71)") (class "Default")
      (node (ref "U$3") (pin "P$71") (pinfunction "D44_P$71") (pintype "bidirectional"))
    )
    (net (code "116") (name "unconnected-(U$3-D45-PadP$72)") (class "Default")
      (node (ref "U$3") (pin "P$72") (pinfunction "D45_P$72") (pintype "bidirectional"))
    )
    (net (code "117") (name "unconnected-(U$3-D46-PadP$73)") (class "Default")
      (node (ref "U$3") (pin "P$73") (pinfunction "D46_P$73") (pintype "bidirectional"))
    )
    (net (code "118") (name "unconnected-(U$3-D47-PadP$74)") (class "Default")
      (node (ref "U$3") (pin "P$74") (pinfunction "D47_P$74") (pintype "bidirectional"))
    )
    (net (code "119") (name "unconnected-(U$3-D48-PadP$75)") (class "Default")
      (node (ref "U$3") (pin "P$75") (pinfunction "D48_P$75") (pintype "bidirectional"))
    )
    (net (code "120") (name "unconnected-(U$3-D49-PadP$76)") (class "Default")
      (node (ref "U$3") (pin "P$76") (pinfunction "D49_P$76") (pintype "bidirectional"))
    )
    (net (code "121") (name "unconnected-(U$3-PadP$81)") (class "Default")
      (node (ref "U$3") (pin "P$81") (pinfunction "P$81_P$81") (pintype "bidirectional"))
    )
    (net (code "122") (name "unconnected-(U$3-PadP$82)") (class "Default")
      (node (ref "U$3") (pin "P$82") (pinfunction "P$82_P$82") (pintype "bidirectional"))
    )
    (net (code "123") (name "unconnected-(U$3-PadP$83)") (class "Default")
      (node (ref "U$3") (pin "P$83") (pinfunction "P$83_P$83") (pintype "bidirectional"))
    )
    (net (code "124") (name "unconnected-(U$3-PadP$84)") (class "Default")
      (node (ref "U$3") (pin "P$84") (pinfunction "P$84_P$84") (pintype "bidirectional"))
    )
    (net (code "125") (name "unconnected-(U$3-PadP$85)") (class "Default")
      (node (ref "U$3") (pin "P$85") (pinfunction "P$85_P$85") (pintype "bidirectional"))
    )
    (net (code "126") (name "unconnected-(U$3-PadP$86)") (class "Default")
      (node (ref "U$3") (pin "P$86") (pinfunction "P$86_P$86") (pintype "bidirectional"))
    )
    (net (code "127") (name "unconnected-(U$3-RST-PadP$10)") (class "Default")
      (node (ref "U$3") (pin "P$10") (pinfunction "RST_P$10") (pintype "bidirectional"))
    )
    (net (code "128") (name "unconnected-(U$3-RX-PadP$11)") (class "Default")
      (node (ref "U$3") (pin "P$11") (pinfunction "RX_P$11") (pintype "bidirectional"))
    )
    (net (code "129") (name "unconnected-(U$3-TX-PadP$12)") (class "Default")
      (node (ref "U$3") (pin "P$12") (pinfunction "TX_P$12") (pintype "bidirectional"))
    )
    (net (code "130") (name "unconnected-(U$3-VIN2-PadP$2)") (class "Default")
      (node (ref "U$3") (pin "P$2") (pinfunction "VIN2_P$2") (pintype "bidirectional"))
    )
    (net (code "131") (name "unconnected-(U$4-ALRT-Pad6)") (class "Default")
      (node (ref "U$4") (pin "6") (pinfunction "ALRT_6") (pintype "bidirectional"))
    )
    (net (code "132") (name "unconnected-(U$7-A0-PadJP1.2)") (class "Default")
      (node (ref "U$7") (pin "JP1.2") (pinfunction "A0_JP1.2") (pintype "bidirectional"))
    )
    (net (code "133") (name "unconnected-(U$7-D0-PadJP1.3)") (class "Default")
      (node (ref "U$7") (pin "JP1.3") (pinfunction "D0_JP1.3") (pintype "bidirectional"))
    )
    (net (code "134") (name "unconnected-(U$7-D3-PadJP2.5)") (class "Default")
      (node (ref "U$7") (pin "JP2.5") (pinfunction "D3_JP2.5") (pintype "bidirectional"))
    )
    (net (code "135") (name "unconnected-(U$7-D4-PadJP2.6)") (class "Default")
      (node (ref "U$7") (pin "JP2.6") (pinfunction "D4_JP2.6") (pintype "bidirectional"))
    )
    (net (code "136") (name "unconnected-(U$7-RST-PadJP1.1)") (class "Default")
      (node (ref "U$7") (pin "JP1.1") (pinfunction "RST_JP1.1") (pintype "bidirectional"))
    )
    (net (code "137") (name "unconnected-(U$7-RX-PadJP2.2)") (class "Default")
      (node (ref "U$7") (pin "JP2.2") (pinfunction "RX_JP2.2") (pintype "bidirectional"))
    )
    (net (code "138") (name "unconnected-(U$7-TX-PadJP2.1)") (class "Default")
      (node (ref "U$7") (pin "JP2.1") (pinfunction "TX_JP2.1") (pintype "bidirectional"))
    )
    (net (code "139") (name "unconnected-(U$10-PadDTR)") (class "Default")
      (node (ref "U$10") (pin "DTR") (pinfunction "DTR_DTR") (pintype "bidirectional"))
    )
    (net (code "140") (name "unconnected-(U$10-PadMIC+)") (class "Default")
      (node (ref "U$10") (pin "MIC+") (pinfunction "MIC+_MIC+") (pintype "bidirectional"))
    )
    (net (code "141") (name "unconnected-(U$10-PadMIC-)") (class "Default")
      (node (ref "U$10") (pin "MIC-") (pinfunction "MIC-_MIC-") (pintype "bidirectional"))
    )
    (net (code "142") (name "unconnected-(U$10-PadNET)") (class "Default")
      (node (ref "U$10") (pin "NET") (pinfunction "NET_NET") (pintype "bidirectional"))
    )
    (net (code "143") (name "unconnected-(U$10-PadRING)") (class "Default")
      (node (ref "U$10") (pin "RING") (pinfunction "RING_RING") (pintype "bidirectional"))
    )
    (net (code "144") (name "unconnected-(U$10-PadRST)") (class "Default")
      (node (ref "U$10") (pin "RST") (pinfunction "RST_RST") (pintype "bidirectional"))
    )
    (net (code "145") (name "unconnected-(U$10-PadSPK+)") (class "Default")
      (node (ref "U$10") (pin "SPK+") (pinfunction "SPK+_SPK+") (pintype "bidirectional"))
    )
    (net (code "146") (name "unconnected-(U$10-PadSPK-)") (class "Default")
      (node (ref "U$10") (pin "SPK-") (pinfunction "SPK-_SPK-") (pintype "bidirectional"))
    )
  )
)
